# Sheet1_4651_MEZ.net
KiCad netlist of a schematic drawn in Altium Designer
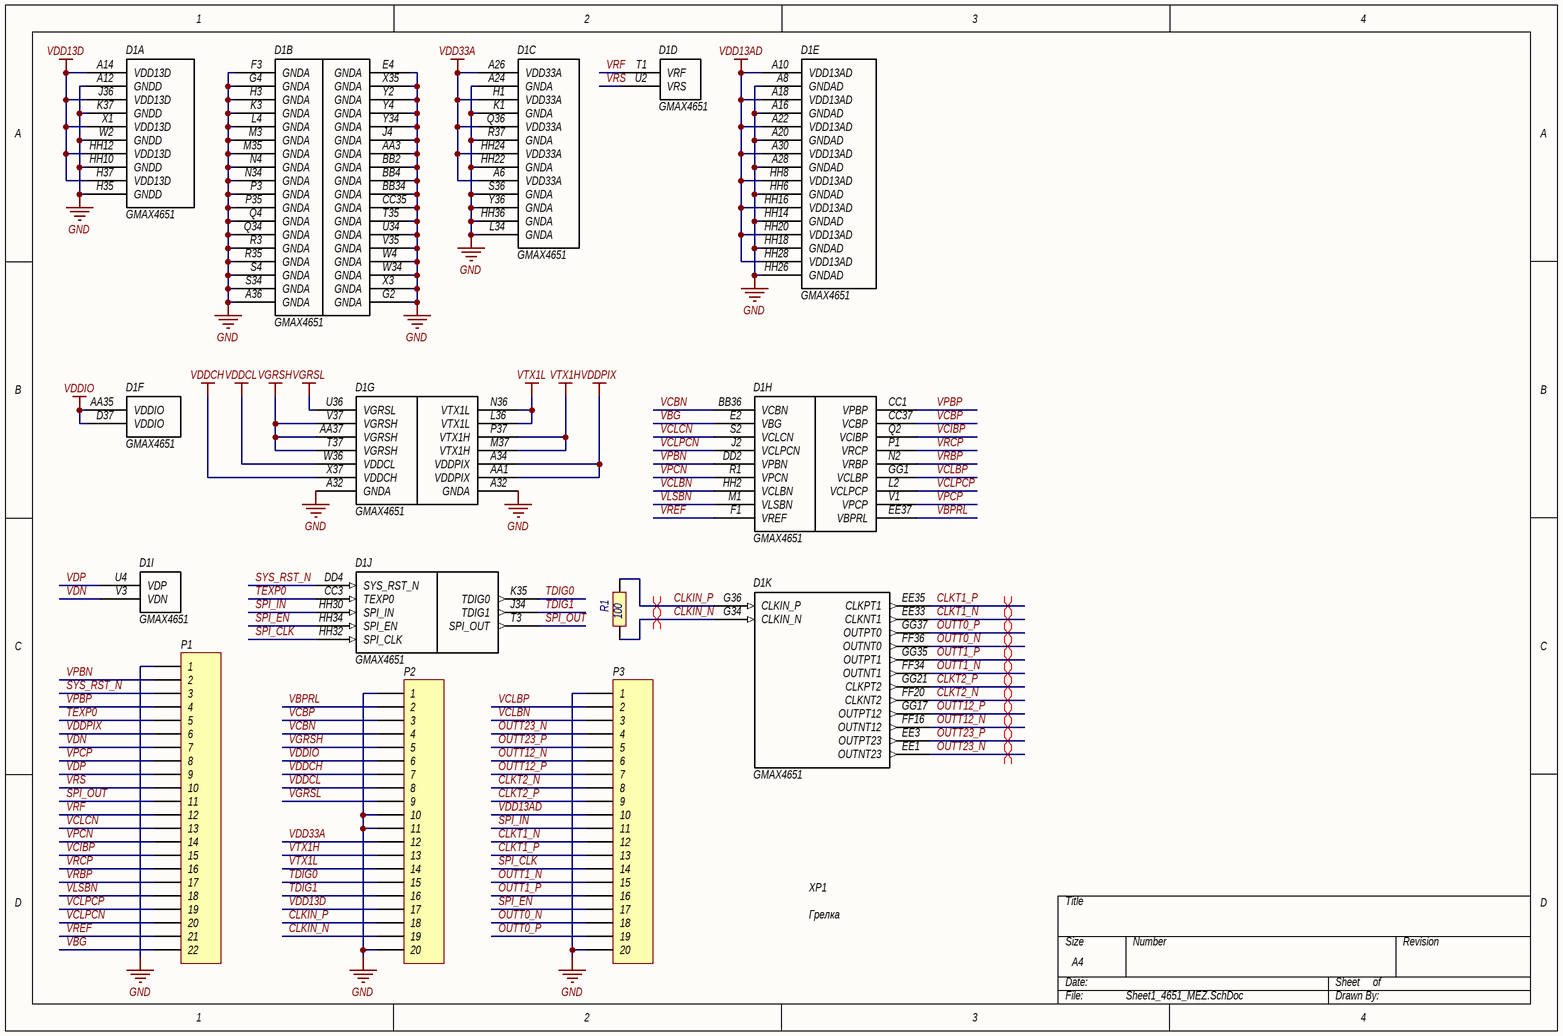
[diagram p0: Sheet1_4651_MEZ.SchDoc]

(export (version "E")
  (design (tool "Eeschema 10.0.6"))
  (components
    (comp (ref "D1") (value "GMAX4651") (footprint "GMAX4651") (libsource (lib "Schlib") (part "GMAX4651")))
    (comp (ref "P1")
      (value "Header 22")
      (footprint "HDR1X22")
      (description "Header, 22-Pin")
      (fields (field (name "PUBLISHER") "Altium Limited"))
      (libsource (lib "Miscellaneous Connectors") (part "Header 22"))
    )
    (comp (ref "P2")
      (value "Header 20")
      (footprint "HDR1X20")
      (description "Header, 20-Pin")
      (fields (field (name "PUBLISHER") "Altium Limited"))
      (libsource (lib "Miscellaneous Connectors") (part "Header 20"))
    )
    (comp (ref "P3")
      (value "Header 20")
      (footprint "HDR1X20")
      (description "Header, 20-Pin")
      (fields (field (name "PUBLISHER") "Altium Limited"))
      (libsource (lib "Miscellaneous Connectors") (part "Header 20"))
    )
    (comp (ref "R1") (value "100") (footprint "RES") (libsource (lib "Schlib") (part "RES")))
    (comp (ref "XP1") (value "Грелка") (footprint "Грелка") (libsource (lib "VPL") (part "Грелка")))
  )
  (nets
    (net (code "1") (name "/CLKIN_N") (class "Default")
      (node (ref "D1") (pin "G34") (pinfunction "CLKIN_N_G34") (pintype "input"))
      (node (ref "P2") (pin "19") (pinfunction "19_19") (pintype "passive"))
      (node (ref "R1") (pin "1") (pinfunction "1_1") (pintype "passive"))
    )
    (net (code "2") (name "/CLKIN_P") (class "Default")
      (node (ref "D1") (pin "G36") (pinfunction "CLKIN_P_G36") (pintype "input"))
      (node (ref "P2") (pin "18") (pinfunction "18_18") (pintype "passive"))
      (node (ref "R1") (pin "2") (pinfunction "2_2") (pintype "passive"))
    )
    (net (code "3") (name "/CLKT1_N") (class "Default")
      (node (ref "D1") (pin "EE33") (pinfunction "CLKNT1_EE33") (pintype "output"))
      (node (ref "P3") (pin "12") (pinfunction "12_12") (pintype "passive"))
    )
    (net (code "4") (name "/CLKT1_P") (class "Default")
      (node (ref "D1") (pin "EE35") (pinfunction "CLKPT1_EE35") (pintype "output"))
      (node (ref "P3") (pin "13") (pinfunction "13_13") (pintype "passive"))
    )
    (net (code "5") (name "/CLKT2_N") (class "Default")
      (node (ref "D1") (pin "FF20") (pinfunction "CLKNT2_FF20") (pintype "output"))
      (node (ref "P3") (pin "8") (pinfunction "8_8") (pintype "passive"))
    )
    (net (code "6") (name "/CLKT2_P") (class "Default")
      (node (ref "D1") (pin "GG21") (pinfunction "CLKPT2_GG21") (pintype "output"))
      (node (ref "P3") (pin "9") (pinfunction "9_9") (pintype "passive"))
    )
    (net (code "7") (name "/OUTT0_N") (class "Default")
      (node (ref "D1") (pin "FF36") (pinfunction "OUTNT0_FF36") (pintype "output"))
      (node (ref "P3") (pin "18") (pinfunction "18_18") (pintype "passive"))
    )
    (net (code "8") (name "/OUTT0_P") (class "Default")
      (node (ref "D1") (pin "GG37") (pinfunction "OUTPT0_GG37") (pintype "output"))
      (node (ref "P3") (pin "19") (pinfunction "19_19") (pintype "passive"))
    )
    (net (code "9") (name "/OUTT1_N") (class "Default")
      (node (ref "D1") (pin "FF34") (pinfunction "OUTNT1_FF34") (pintype "output"))
      (node (ref "P3") (pin "15") (pinfunction "15_15") (pintype "passive"))
    )
    (net (code "10") (name "/OUTT1_P") (class "Default")
      (node (ref "D1") (pin "GG35") (pinfunction "OUTPT1_GG35") (pintype "output"))
      (node (ref "P3") (pin "16") (pinfunction "16_16") (pintype "passive"))
    )
    (net (code "11") (name "/OUTT12_N") (class "Default")
      (node (ref "D1") (pin "FF16") (pinfunction "OUTNT12_FF16") (pintype "output"))
      (node (ref "P3") (pin "6") (pinfunction "6_6") (pintype "passive"))
    )
    (net (code "12") (name "/OUTT12_P") (class "Default")
      (node (ref "D1") (pin "GG17") (pinfunction "OUTPT12_GG17") (pintype "output"))
      (node (ref "P3") (pin "7") (pinfunction "7_7") (pintype "passive"))
    )
    (net (code "13") (name "/OUTT23_N") (class "Default")
      (node (ref "D1") (pin "EE1") (pinfunction "OUTNT23_EE1") (pintype "output"))
      (node (ref "P3") (pin "4") (pinfunction "4_4") (pintype "passive"))
    )
    (net (code "14") (name "/OUTT23_P") (class "Default")
      (node (ref "D1") (pin "EE3") (pinfunction "OUTPT23_EE3") (pintype "output"))
      (node (ref "P3") (pin "5") (pinfunction "5_5") (pintype "passive"))
    )
    (net (code "15") (name "/SPI_CLK") (class "Default")
      (node (ref "D1") (pin "HH32") (pinfunction "SPI_CLK_HH32") (pintype "input"))
      (node (ref "P3") (pin "14") (pinfunction "14_14") (pintype "passive"))
    )
    (net (code "16") (name "/SPI_EN") (class "Default")
      (node (ref "D1") (pin "HH34") (pinfunction "SPI_EN_HH34") (pintype "input"))
      (node (ref "P3") (pin "17") (pinfunction "17_17") (pintype "passive"))
    )
    (net (code "17") (name "/SPI_IN") (class "Default")
      (node (ref "D1") (pin "HH30") (pinfunction "SPI_IN_HH30") (pintype "input"))
      (node (ref "P3") (pin "11") (pinfunction "11_11") (pintype "passive"))
    )
    (net (code "18") (name "/SPI_OUT") (class "Default")
      (node (ref "D1") (pin "T3") (pinfunction "SPI_OUT_T3") (pintype "output"))
      (node (ref "P1") (pin "11") (pinfunction "11_11") (pintype "passive"))
    )
    (net (code "19") (name "/SYS_RST_N") (class "Default")
      (node (ref "D1") (pin "DD4") (pinfunction "SYS_RST_N_DD4") (pintype "input"))
      (node (ref "P1") (pin "3") (pinfunction "3_3") (pintype "passive"))
    )
    (net (code "20") (name "/TDIG0") (class "Default")
      (node (ref "D1") (pin "K35") (pinfunction "TDIG0_K35") (pintype "output"))
      (node (ref "P2") (pin "15") (pinfunction "15_15") (pintype "passive"))
    )
    (net (code "21") (name "/TDIG1") (class "Default")
      (node (ref "D1") (pin "J34") (pinfunction "TDIG1_J34") (pintype "output"))
      (node (ref "P2") (pin "16") (pinfunction "16_16") (pintype "passive"))
    )
    (net (code "22") (name "/TEXP0") (class "Default")
      (node (ref "D1") (pin "CC3") (pinfunction "TEXP0_CC3") (pintype "input"))
      (node (ref "P1") (pin "5") (pinfunction "5_5") (pintype "passive"))
    )
    (net (code "23") (name "/VBG") (class "Default")
      (node (ref "D1") (pin "E2") (pinfunction "VBG_E2") (pintype "passive"))
      (node (ref "P1") (pin "22") (pinfunction "22_22") (pintype "passive"))
    )
    (net (code "24") (name "/VBPRL") (class "Default")
      (node (ref "D1") (pin "EE37") (pinfunction "VBPRL_EE37") (pintype "passive"))
      (node (ref "P2") (pin "2") (pinfunction "2_2") (pintype "passive"))
    )
    (net (code "25") (name "/VCBN") (class "Default")
      (node (ref "D1") (pin "BB36") (pinfunction "VCBN_BB36") (pintype "passive"))
      (node (ref "P2") (pin "4") (pinfunction "4_4") (pintype "passive"))
    )
    (net (code "26") (name "/VCBP") (class "Default")
      (node (ref "D1") (pin "CC37") (pinfunction "VCBP_CC37") (pintype "passive"))
      (node (ref "P2") (pin "3") (pinfunction "3_3") (pintype "passive"))
    )
    (net (code "27") (name "/VCIBP") (class "Default")
      (node (ref "D1") (pin "Q2") (pinfunction "VCIBP_Q2") (pintype "passive"))
      (node (ref "P1") (pin "15") (pinfunction "15_15") (pintype "passive"))
    )
    (net (code "28") (name "/VCLBN") (class "Default")
      (node (ref "D1") (pin "HH2") (pinfunction "VCLBN_HH2") (pintype "passive"))
      (node (ref "P3") (pin "3") (pinfunction "3_3") (pintype "passive"))
    )
    (net (code "29") (name "/VCLBP") (class "Default")
      (node (ref "D1") (pin "GG1") (pinfunction "VCLBP_GG1") (pintype "passive"))
      (node (ref "P3") (pin "2") (pinfunction "2_2") (pintype "passive"))
    )
    (net (code "30") (name "/VCLCN") (class "Default")
      (node (ref "D1") (pin "S2") (pinfunction "VCLCN_S2") (pintype "passive"))
      (node (ref "P1") (pin "13") (pinfunction "13_13") (pintype "passive"))
    )
    (net (code "31") (name "/VCLPCN") (class "Default")
      (node (ref "D1") (pin "J2") (pinfunction "VCLPCN_J2") (pintype "passive"))
      (node (ref "P1") (pin "20") (pinfunction "20_20") (pintype "passive"))
    )
    (net (code "32") (name "/VCLPCP") (class "Default")
      (node (ref "D1") (pin "L2") (pinfunction "VCLPCP_L2") (pintype "passive"))
      (node (ref "P1") (pin "19") (pinfunction "19_19") (pintype "passive"))
    )
    (net (code "33") (name "/VDN") (class "Default")
      (node (ref "D1") (pin "V3") (pinfunction "VDN_V3") (pintype "passive"))
      (node (ref "P1") (pin "7") (pinfunction "7_7") (pintype "passive"))
    )
    (net (code "34") (name "/VDP") (class "Default")
      (node (ref "D1") (pin "U4") (pinfunction "VDP_U4") (pintype "passive"))
      (node (ref "P1") (pin "9") (pinfunction "9_9") (pintype "passive"))
    )
    (net (code "35") (name "/VLSBN") (class "Default")
      (node (ref "D1") (pin "M1") (pinfunction "VLSBN_M1") (pintype "passive"))
      (node (ref "P1") (pin "18") (pinfunction "18_18") (pintype "passive"))
    )
    (net (code "36") (name "/VPBN") (class "Default")
      (node (ref "D1") (pin "DD2") (pinfunction "VPBN_DD2") (pintype "passive"))
      (node (ref "P1") (pin "2") (pinfunction "2_2") (pintype "passive"))
    )
    (net (code "37") (name "/VPBP") (class "Default")
      (node (ref "D1") (pin "CC1") (pinfunction "VPBP_CC1") (pintype "passive"))
      (node (ref "P1") (pin "4") (pinfunction "4_4") (pintype "passive"))
    )
    (net (code "38") (name "/VPCN") (class "Default")
      (node (ref "D1") (pin "R1") (pinfunction "VPCN_R1") (pintype "passive"))
      (node (ref "P1") (pin "14") (pinfunction "14_14") (pintype "passive"))
    )
    (net (code "39") (name "/VPCP") (class "Default")
      (node (ref "D1") (pin "V1") (pinfunction "VPCP_V1") (pintype "passive"))
      (node (ref "P1") (pin "8") (pinfunction "8_8") (pintype "passive"))
    )
    (net (code "40") (name "/VRBP") (class "Default")
      (node (ref "D1") (pin "N2") (pinfunction "VRBP_N2") (pintype "passive"))
      (node (ref "P1") (pin "17") (pinfunction "17_17") (pintype "passive"))
    )
    (net (code "41") (name "/VRCP") (class "Default")
      (node (ref "D1") (pin "P1") (pinfunction "VRCP_P1") (pintype "passive"))
      (node (ref "P1") (pin "16") (pinfunction "16_16") (pintype "passive"))
    )
    (net (code "42") (name "/VREF") (class "Default")
      (node (ref "D1") (pin "F1") (pinfunction "VREF_F1") (pintype "passive"))
      (node (ref "P1") (pin "21") (pinfunction "21_21") (pintype "passive"))
    )
    (net (code "43") (name "/VRF") (class "Default")
      (node (ref "D1") (pin "T1") (pinfunction "VRF_T1") (pintype "passive"))
      (node (ref "P1") (pin "12") (pinfunction "12_12") (pintype "passive"))
    )
    (net (code "44") (name "/VRS") (class "Default")
      (node (ref "D1") (pin "U2") (pinfunction "VRS_U2") (pintype "passive"))
      (node (ref "P1") (pin "10") (pinfunction "10_10") (pintype "passive"))
    )
    (net (code "45") (name "GND") (class "Default")
      (node (ref "D1") (pin "A12") (pinfunction "GNDD_A12") (pintype "passive"))
      (node (ref "D1") (pin "A16") (pinfunction "GNDAD_A16") (pintype "passive"))
      (node (ref "D1") (pin "A20") (pinfunction "GNDAD_A20") (pintype "passive"))
      (node (ref "D1") (pin "A24") (pinfunction "GNDA_A24") (pintype "passive"))
      (node (ref "D1") (pin "A28") (pinfunction "GNDAD_A28") (pintype "passive"))
      (node (ref "D1") (pin "A32") (pinfunction "GNDA_A32") (pintype "passive"))
      (node (ref "D1") (pin "A36") (pinfunction "GNDA_A36") (pintype "passive"))
      (node (ref "D1") (pin "A8") (pinfunction "GNDAD_A8") (pintype "passive"))
      (node (ref "D1") (pin "AA3") (pinfunction "GNDA_AA3") (pintype "passive"))
      (node (ref "D1") (pin "BB2") (pinfunction "GNDA_BB2") (pintype "passive"))
      (node (ref "D1") (pin "BB34") (pinfunction "GNDA_BB34") (pintype "passive"))
      (node (ref "D1") (pin "BB4") (pinfunction "GNDA_BB4") (pintype "passive"))
      (node (ref "D1") (pin "CC35") (pinfunction "GNDA_CC35") (pintype "passive"))
      (node (ref "D1") (pin "E4") (pinfunction "GNDA_E4") (pintype "passive"))
      (node (ref "D1") (pin "F3") (pinfunction "GNDA_F3") (pintype "passive"))
      (node (ref "D1") (pin "G2") (pinfunction "GNDA_G2") (pintype "passive"))
      (node (ref "D1") (pin "G4") (pinfunction "GNDA_G4") (pintype "passive"))
      (node (ref "D1") (pin "H3") (pinfunction "GNDA_H3") (pintype "passive"))
      (node (ref "D1") (pin "H35") (pinfunction "GNDD_H35") (pintype "passive"))
      (node (ref "D1") (pin "HH10") (pinfunction "GNDD_HH10") (pintype "passive"))
      (node (ref "D1") (pin "HH14") (pinfunction "GNDAD_HH14") (pintype "passive"))
      (node (ref "D1") (pin "HH18") (pinfunction "GNDAD_HH18") (pintype "passive"))
      (node (ref "D1") (pin "HH22") (pinfunction "GNDA_HH22") (pintype "passive"))
      (node (ref "D1") (pin "HH26") (pinfunction "GNDAD_HH26") (pintype "passive"))
      (node (ref "D1") (pin "HH36") (pinfunction "GNDA_HH36") (pintype "passive"))
      (node (ref "D1") (pin "HH6") (pinfunction "GNDAD_HH6") (pintype "passive"))
      (node (ref "D1") (pin "J4") (pinfunction "GNDA_J4") (pintype "passive"))
      (node (ref "D1") (pin "K1") (pinfunction "GNDA_K1") (pintype "passive"))
      (node (ref "D1") (pin "K3") (pinfunction "GNDA_K3") (pintype "passive"))
      (node (ref "D1") (pin "K37") (pinfunction "GNDD_K37") (pintype "passive"))
      (node (ref "D1") (pin "L34") (pinfunction "GNDA_L34") (pintype "passive"))
      (node (ref "D1") (pin "L4") (pinfunction "GNDA_L4") (pintype "passive"))
      (node (ref "D1") (pin "M3") (pinfunction "GNDA_M3") (pintype "passive"))
      (node (ref "D1") (pin "M35") (pinfunction "GNDA_M35") (pintype "passive"))
      (node (ref "D1") (pin "N34") (pinfunction "GNDA_N34") (pintype "passive"))
      (node (ref "D1") (pin "N4") (pinfunction "GNDA_N4") (pintype "passive"))
      (node (ref "D1") (pin "P3") (pinfunction "GNDA_P3") (pintype "passive"))
      (node (ref "D1") (pin "P35") (pinfunction "GNDA_P35") (pintype "passive"))
      (node (ref "D1") (pin "Q34") (pinfunction "GNDA_Q34") (pintype "passive"))
      (node (ref "D1") (pin "Q4") (pinfunction "GNDA_Q4") (pintype "passive"))
      (node (ref "D1") (pin "R3") (pinfunction "GNDA_R3") (pintype "passive"))
      (node (ref "D1") (pin "R35") (pinfunction "GNDA_R35") (pintype "passive"))
      (node (ref "D1") (pin "R37") (pinfunction "GNDA_R37") (pintype "passive"))
      (node (ref "D1") (pin "S34") (pinfunction "GNDA_S34") (pintype "passive"))
      (node (ref "D1") (pin "S36") (pinfunction "GNDA_S36") (pintype "passive"))
      (node (ref "D1") (pin "S4") (pinfunction "GNDA_S4") (pintype "passive"))
      (node (ref "D1") (pin "T35") (pinfunction "GNDA_T35") (pintype "passive"))
      (node (ref "D1") (pin "U34") (pinfunction "GNDA_U34") (pintype "passive"))
      (node (ref "D1") (pin "V35") (pinfunction "GNDA_V35") (pintype "passive"))
      (node (ref "D1") (pin "W2") (pinfunction "GNDD_W2") (pintype "passive"))
      (node (ref "D1") (pin "W34") (pinfunction "GNDA_W34") (pintype "passive"))
      (node (ref "D1") (pin "W4") (pinfunction "GNDA_W4") (pintype "passive"))
      (node (ref "D1") (pin "X3") (pinfunction "GNDA_X3") (pintype "passive"))
      (node (ref "D1") (pin "X35") (pinfunction "GNDA_X35") (pintype "passive"))
      (node (ref "D1") (pin "Y2") (pinfunction "GNDA_Y2") (pintype "passive"))
      (node (ref "D1") (pin "Y34") (pinfunction "GNDA_Y34") (pintype "passive"))
      (node (ref "D1") (pin "Y36") (pinfunction "GNDA_Y36") (pintype "passive"))
      (node (ref "D1") (pin "Y4") (pinfunction "GNDA_Y4") (pintype "passive"))
      (node (ref "P1") (pin "1") (pinfunction "1_1") (pintype "passive"))
      (node (ref "P2") (pin "1") (pinfunction "1_1") (pintype "passive"))
      (node (ref "P2") (pin "10") (pinfunction "10_10") (pintype "passive"))
      (node (ref "P2") (pin "11") (pinfunction "11_11") (pintype "passive"))
      (node (ref "P2") (pin "20") (pinfunction "20_20") (pintype "passive"))
      (node (ref "P3") (pin "1") (pinfunction "1_1") (pintype "passive"))
      (node (ref "P3") (pin "20") (pinfunction "20_20") (pintype "passive"))
    )
    (net (code "46") (name "VDD13AD") (class "Default")
      (node (ref "D1") (pin "A10") (pinfunction "VDD13AD_A10") (pintype "passive"))
      (node (ref "D1") (pin "A18") (pinfunction "VDD13AD_A18") (pintype "passive"))
      (node (ref "D1") (pin "A22") (pinfunction "VDD13AD_A22") (pintype "passive"))
      (node (ref "D1") (pin "A30") (pinfunction "VDD13AD_A30") (pintype "passive"))
      (node (ref "D1") (pin "HH16") (pinfunction "VDD13AD_HH16") (pintype "passive"))
      (node (ref "D1") (pin "HH20") (pinfunction "VDD13AD_HH20") (pintype "passive"))
      (node (ref "D1") (pin "HH28") (pinfunction "VDD13AD_HH28") (pintype "passive"))
      (node (ref "D1") (pin "HH8") (pinfunction "VDD13AD_HH8") (pintype "passive"))
      (node (ref "P3") (pin "10") (pinfunction "10_10") (pintype "passive"))
    )
    (net (code "47") (name "VDD13D") (class "Default")
      (node (ref "D1") (pin "A14") (pinfunction "VDD13D_A14") (pintype "passive"))
      (node (ref "D1") (pin "H37") (pinfunction "VDD13D_H37") (pintype "passive"))
      (node (ref "D1") (pin "HH12") (pinfunction "VDD13D_HH12") (pintype "passive"))
      (node (ref "D1") (pin "J36") (pinfunction "VDD13D_J36") (pintype "passive"))
      (node (ref "D1") (pin "X1") (pinfunction "VDD13D_X1") (pintype "passive"))
      (node (ref "P2") (pin "17") (pinfunction "17_17") (pintype "passive"))
    )
    (net (code "48") (name "VDD33A") (class "Default")
      (node (ref "D1") (pin "A26") (pinfunction "VDD33A_A26") (pintype "passive"))
      (node (ref "D1") (pin "A6") (pinfunction "VDD33A_A6") (pintype "passive"))
      (node (ref "D1") (pin "H1") (pinfunction "VDD33A_H1") (pintype "passive"))
      (node (ref "D1") (pin "HH24") (pinfunction "VDD33A_HH24") (pintype "passive"))
      (node (ref "D1") (pin "Q36") (pinfunction "VDD33A_Q36") (pintype "passive"))
      (node (ref "P2") (pin "12") (pinfunction "12_12") (pintype "passive"))
    )
    (net (code "49") (name "VDDCH") (class "Default")
      (node (ref "D1") (pin "X37") (pinfunction "VDDCH_X37") (pintype "passive"))
      (node (ref "P2") (pin "7") (pinfunction "7_7") (pintype "passive"))
    )
    (net (code "50") (name "VDDCL") (class "Default")
      (node (ref "D1") (pin "W36") (pinfunction "VDDCL_W36") (pintype "passive"))
      (node (ref "P2") (pin "8") (pinfunction "8_8") (pintype "passive"))
    )
    (net (code "51") (name "VDDIO") (class "Default")
      (node (ref "D1") (pin "AA35") (pinfunction "VDDIO_AA35") (pintype "passive"))
      (node (ref "D1") (pin "D37") (pinfunction "VDDIO_D37") (pintype "passive"))
      (node (ref "P2") (pin "6") (pinfunction "6_6") (pintype "passive"))
    )
    (net (code "52") (name "VDDPIX") (class "Default")
      (node (ref "D1") (pin "A34") (pinfunction "VDDPIX_A34") (pintype "passive"))
      (node (ref "D1") (pin "AA1") (pinfunction "VDDPIX_AA1") (pintype "passive"))
      (node (ref "P1") (pin "6") (pinfunction "6_6") (pintype "passive"))
    )
    (net (code "53") (name "VGRSH") (class "Default")
      (node (ref "D1") (pin "AA37") (pinfunction "VGRSH_AA37") (pintype "passive"))
      (node (ref "D1") (pin "T37") (pinfunction "VGRSH_T37") (pintype "passive"))
      (node (ref "D1") (pin "V37") (pinfunction "VGRSH_V37") (pintype "passive"))
      (node (ref "P2") (pin "5") (pinfunction "5_5") (pintype "passive"))
    )
    (net (code "54") (name "VGRSL") (class "Default")
      (node (ref "D1") (pin "U36") (pinfunction "VGRSL_U36") (pintype "passive"))
      (node (ref "P2") (pin "9") (pinfunction "9_9") (pintype "passive"))
    )
    (net (code "55") (name "VTX1H") (class "Default")
      (node (ref "D1") (pin "M37") (pinfunction "VTX1H_M37") (pintype "passive"))
      (node (ref "D1") (pin "P37") (pinfunction "VTX1H_P37") (pintype "passive"))
      (node (ref "P2") (pin "13") (pinfunction "13_13") (pintype "passive"))
    )
    (net (code "56") (name "VTX1L") (class "Default")
      (node (ref "D1") (pin "L36") (pinfunction "VTX1L_L36") (pintype "passive"))
      (node (ref "D1") (pin "N36") (pinfunction "VTX1L_N36") (pintype "passive"))
      (node (ref "P2") (pin "14") (pinfunction "14_14") (pintype "passive"))
    )
  )
)
